# design.net
KiCad netlist of a schematic drawn in Altium Designer
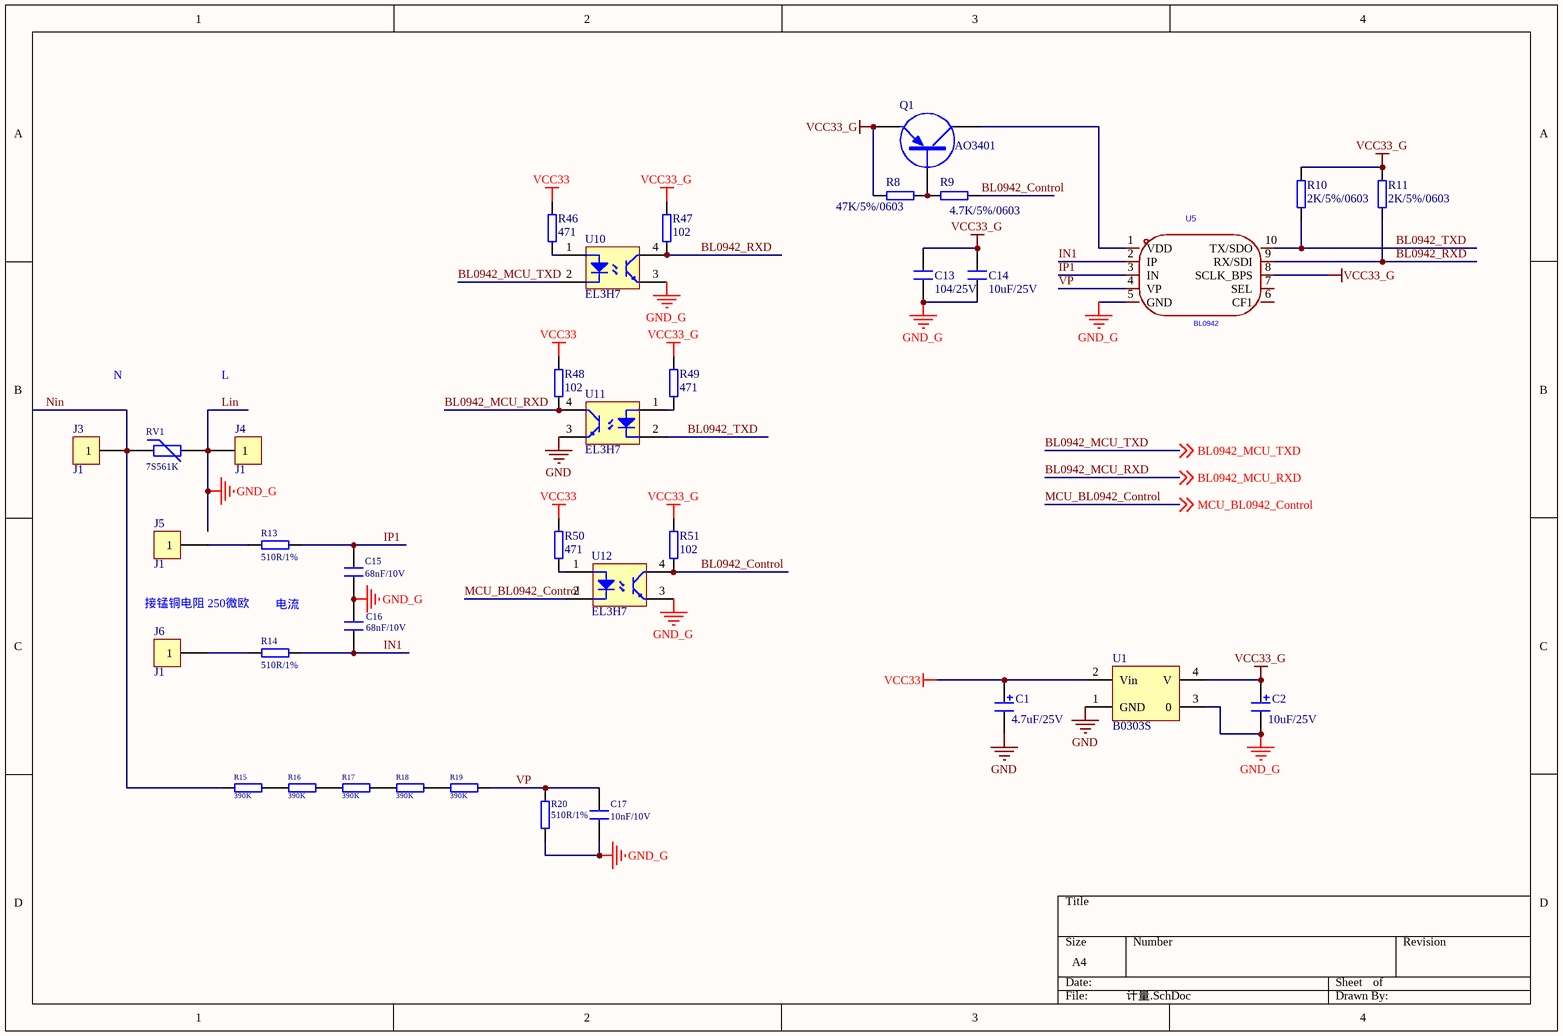
[diagram p0: 计量.SchDoc]

(export (version "E")
  (design (tool "Eeschema 10.0.6"))
  (components
    (comp (ref "C1") (value "4.7uF/25V") (footprint "0805R") (libsource (lib "ES_Schematic") (part "CAP+")))
    (comp (ref "C2") (value "10uF/25V") (footprint "0805R") (libsource (lib "ES_Schematic") (part "CAP+")))
    (comp (ref "C13") (value "104/25V") (footprint "0603R") (libsource (lib "ES_Schematic") (part "CAP_1")))
    (comp (ref "C14") (value "10uF/25V") (footprint "0603R") (libsource (lib "ES_Schematic") (part "CAP_1")))
    (comp (ref "C15") (value "68nF/10V") (footprint "0603R") (libsource (lib "ES_Schematic") (part "CAP")))
    (comp (ref "C16") (value "68nF/10V") (footprint "0603R") (libsource (lib "ES_Schematic") (part "CAP")))
    (comp (ref "C17") (value "10nF/10V") (footprint "0603R") (libsource (lib "ES_Schematic") (part "CAP")))
    (comp (ref "J3") (value "J1") (footprint "贴片焊盘V1（3*2椭圆）") (libsource (lib "") (part "J1_1")))
    (comp (ref "J4") (value "J1") (footprint "贴片焊盘V1（3*2椭圆）") (libsource (lib "ES_Schematic") (part "J1")))
    (comp (ref "J5") (value "J1") (footprint "贴片焊盘V1（3*2椭圆）") (libsource (lib "") (part "J1_1")))
    (comp (ref "J6") (value "J1") (footprint "贴片焊盘V1（3*2椭圆）") (libsource (lib "") (part "J1_1")))
    (comp (ref "Q1") (value "AO3401") (footprint "SOT-23") (libsource (lib "ES_Schematic") (part "PNP")))
    (comp (ref "R8") (value "47K/5%/0603") (footprint "0603R") (libsource (lib "ES_Schematic") (part "RES")))
    (comp (ref "R9") (value "4.7K/5%/0603") (footprint "0603R") (libsource (lib "ES_Schematic") (part "RES")))
    (comp (ref "R10") (value "2K/5%/0603") (footprint "0603R") (libsource (lib "ES_Schematic") (part "RES")))
    (comp (ref "R11") (value "2K/5%/0603") (footprint "0603R") (libsource (lib "ES_Schematic") (part "RES")))
    (comp (ref "R13") (value "510R/1%") (footprint "0603R") (libsource (lib "ES_Schematic") (part "RES")))
    (comp (ref "R14") (value "510R/1%") (footprint "0603R") (libsource (lib "ES_Schematic") (part "RES")))
    (comp (ref "R15") (value "390K") (footprint "0805R") (libsource (lib "ES_Schematic") (part "RES")))
    (comp (ref "R16") (value "390K") (footprint "0805R") (libsource (lib "ES_Schematic") (part "RES")))
    (comp (ref "R17") (value "390K") (footprint "0805R") (libsource (lib "ES_Schematic") (part "RES")))
    (comp (ref "R18") (value "390K") (footprint "0805R") (libsource (lib "ES_Schematic") (part "RES")))
    (comp (ref "R19") (value "390K") (footprint "0805R") (libsource (lib "ES_Schematic") (part "RES")))
    (comp (ref "R20") (value "510R/1%") (footprint "0603R") (libsource (lib "ES_Schematic") (part "RES")))
    (comp (ref "R46") (value "471") (footprint "0603R") (libsource (lib "ES_Schematic") (part "RES")))
    (comp (ref "R47") (value "102") (footprint "0603R") (libsource (lib "ES_Schematic") (part "RES")))
    (comp (ref "R48") (value "102") (footprint "0603R") (libsource (lib "ES_Schematic") (part "RES")))
    (comp (ref "R49") (value "471") (footprint "0603R") (libsource (lib "ES_Schematic") (part "RES")))
    (comp (ref "R50") (value "471") (footprint "0603R") (libsource (lib "ES_Schematic") (part "RES")))
    (comp (ref "R51") (value "102") (footprint "0603R") (libsource (lib "ES_Schematic") (part "RES")))
    (comp (ref "RV1")
      (value "7S561K")
      (footprint "10D821K")
      (description "Varistor (Voltage-Sensitive Resistor)")
      (fields (field (name "PUBLISHER") "Altium Limited"))
      (libsource (lib "Miscellaneous Devices") (part "Res Varistor"))
    )
    (comp (ref "U1") (value "B0303S") (footprint "B1205S-1WR3") (libsource (lib "sangjian") (part "B0505S")))
    (comp (ref "U5")
      (value "BL0942")
      (footprint "BL0942-10pin")
      (fields (field (name "MANUFACTURER") "BL(上海贝岭)"))
      (libsource (lib "altium-import") (part "root_0_BL0942_C2837510_"))
    )
    (comp (ref "U10")
      (value "EL3H7")
      (footprint "EL3H7")
      (libsource (lib "ES_Schematic") (part "Optical_Coupler_1"))
    )
    (comp (ref "U11") (value "EL3H7") (footprint "EL3H7") (libsource (lib "") (part "Optical_Coupler_1_1")))
    (comp (ref "U12")
      (value "EL3H7")
      (footprint "EL3H7")
      (libsource (lib "ES_Schematic") (part "Optical_Coupler_1"))
    )
  )
  (nets
    (net (code "1") (name "/BL0942_Control") (class "Default")
      (node (ref "R51") (pin "1") (pinfunction "1_1") (pintype "passive"))
      (node (ref "R9") (pin "2") (pinfunction "2_2") (pintype "passive"))
      (node (ref "U12") (pin "4") (pinfunction "C_4") (pintype "passive"))
    )
    (net (code "2") (name "/BL0942_RXD") (class "Default")
      (node (ref "R11") (pin "1") (pinfunction "1_1") (pintype "passive"))
      (node (ref "R47") (pin "1") (pinfunction "1_1") (pintype "passive"))
      (node (ref "U10") (pin "4") (pinfunction "C_4") (pintype "passive"))
      (node (ref "U5") (pin "9") (pinfunction "RX/SDI_9") (pintype "passive"))
    )
    (net (code "3") (name "/BL0942_TXD") (class "Default")
      (node (ref "R10") (pin "1") (pinfunction "1_1") (pintype "passive"))
      (node (ref "U11") (pin "2") (pinfunction "K_2") (pintype "passive"))
      (node (ref "U5") (pin "10") (pinfunction "TX/SDO_10") (pintype "passive"))
    )
    (net (code "4") (name "/IN1") (class "Default")
      (node (ref "C16") (pin "1") (pinfunction "1_1") (pintype "passive"))
      (node (ref "R14") (pin "2") (pinfunction "2_2") (pintype "passive"))
      (node (ref "U5") (pin "2") (pinfunction "IP_2") (pintype "passive"))
    )
    (net (code "5") (name "/IP1") (class "Default")
      (node (ref "C15") (pin "1") (pinfunction "1_1") (pintype "passive"))
      (node (ref "R13") (pin "2") (pinfunction "2_2") (pintype "passive"))
      (node (ref "U5") (pin "3") (pinfunction "IN_3") (pintype "passive"))
    )
    (net (code "6") (name "/Nin") (class "Default")
      (node (ref "J3") (pin "1") (pinfunction "1_1") (pintype "passive"))
      (node (ref "R15") (pin "2") (pinfunction "2_2") (pintype "passive"))
      (node (ref "RV1") (pin "1") (pinfunction "1_1") (pintype "passive"))
    )
    (net (code "7") (name "/VP") (class "Default")
      (node (ref "C17") (pin "1") (pinfunction "1_1") (pintype "passive"))
      (node (ref "R19") (pin "1") (pinfunction "1_1") (pintype "passive"))
      (node (ref "R20") (pin "2") (pinfunction "2_2") (pintype "passive"))
      (node (ref "U5") (pin "4") (pinfunction "VP_4") (pintype "passive"))
    )
    (net (code "8") (name "BL0942_MCU_RXD") (class "Default")
      (node (ref "R48") (pin "1") (pinfunction "1_1") (pintype "passive"))
      (node (ref "U11") (pin "4") (pinfunction "C_4") (pintype "passive"))
    )
    (net (code "9") (name "BL0942_MCU_TXD") (class "Default")
      (node (ref "U10") (pin "2") (pinfunction "K_2") (pintype "passive"))
    )
    (net (code "10") (name "GND") (class "Default")
      (node (ref "C1") (pin "2") (pinfunction "2_2") (pintype "passive"))
      (node (ref "U1") (pin "1") (pinfunction "GND_1") (pintype "passive"))
      (node (ref "U11") (pin "3") (pinfunction "E_3") (pintype "passive"))
    )
    (net (code "11") (name "GND_G") (class "Default")
      (node (ref "C13") (pin "1") (pinfunction "1_1") (pintype "passive"))
      (node (ref "C14") (pin "1") (pinfunction "1_1") (pintype "passive"))
      (node (ref "C15") (pin "2") (pinfunction "2_2") (pintype "passive"))
      (node (ref "C16") (pin "2") (pinfunction "2_2") (pintype "passive"))
      (node (ref "C17") (pin "2") (pinfunction "2_2") (pintype "passive"))
      (node (ref "C2") (pin "2") (pinfunction "2_2") (pintype "passive"))
      (node (ref "J4") (pin "1") (pinfunction "1_1") (pintype "passive"))
      (node (ref "R20") (pin "1") (pinfunction "1_1") (pintype "passive"))
      (node (ref "RV1") (pin "2") (pinfunction "2_2") (pintype "passive"))
      (node (ref "U1") (pin "3") (pinfunction "0_3") (pintype "passive"))
      (node (ref "U10") (pin "3") (pinfunction "E_3") (pintype "passive"))
      (node (ref "U12") (pin "3") (pinfunction "E_3") (pintype "passive"))
      (node (ref "U5") (pin "5") (pinfunction "GND_5") (pintype "passive"))
    )
    (net (code "12") (name "MCU_BL0942_Control") (class "Default")
      (node (ref "U12") (pin "2") (pinfunction "K_2") (pintype "passive"))
    )
    (net (code "13") (name "Net-(J5-Pad1)") (class "Default")
      (node (ref "J5") (pin "1") (pinfunction "1_1") (pintype "passive"))
      (node (ref "R13") (pin "1") (pinfunction "1_1") (pintype "passive"))
    )
    (net (code "14") (name "Net-(J6-Pad1)") (class "Default")
      (node (ref "J6") (pin "1") (pinfunction "1_1") (pintype "passive"))
      (node (ref "R14") (pin "1") (pinfunction "1_1") (pintype "passive"))
    )
    (net (code "15") (name "Net-(Q1-B)") (class "Default")
      (node (ref "Q1") (pin "1") (pinfunction "B_1") (pintype "passive"))
      (node (ref "R8") (pin "1") (pinfunction "1_1") (pintype "passive"))
      (node (ref "R9") (pin "1") (pinfunction "1_1") (pintype "passive"))
    )
    (net (code "16") (name "Net-(Q1-C)") (class "Default")
      (node (ref "Q1") (pin "3") (pinfunction "C_3") (pintype "passive"))
      (node (ref "U5") (pin "1") (pinfunction "VDD_1") (pintype "passive"))
    )
    (net (code "17") (name "Net-(R15-Pad1)") (class "Default")
      (node (ref "R15") (pin "1") (pinfunction "1_1") (pintype "passive"))
      (node (ref "R16") (pin "2") (pinfunction "2_2") (pintype "passive"))
    )
    (net (code "18") (name "Net-(R16-Pad1)") (class "Default")
      (node (ref "R16") (pin "1") (pinfunction "1_1") (pintype "passive"))
      (node (ref "R17") (pin "2") (pinfunction "2_2") (pintype "passive"))
    )
    (net (code "19") (name "Net-(R17-Pad1)") (class "Default")
      (node (ref "R17") (pin "1") (pinfunction "1_1") (pintype "passive"))
      (node (ref "R18") (pin "2") (pinfunction "2_2") (pintype "passive"))
    )
    (net (code "20") (name "Net-(R18-Pad1)") (class "Default")
      (node (ref "R18") (pin "1") (pinfunction "1_1") (pintype "passive"))
      (node (ref "R19") (pin "2") (pinfunction "2_2") (pintype "passive"))
    )
    (net (code "21") (name "Net-(U10-A)") (class "Default")
      (node (ref "R46") (pin "2") (pinfunction "2_2") (pintype "passive"))
      (node (ref "U10") (pin "1") (pinfunction "A_1") (pintype "passive"))
    )
    (net (code "22") (name "Net-(U11-A)") (class "Default")
      (node (ref "R49") (pin "2") (pinfunction "2_2") (pintype "passive"))
      (node (ref "U11") (pin "1") (pinfunction "A_1") (pintype "passive"))
    )
    (net (code "23") (name "Net-(U12-A)") (class "Default")
      (node (ref "R50") (pin "2") (pinfunction "2_2") (pintype "passive"))
      (node (ref "U12") (pin "1") (pinfunction "A_1") (pintype "passive"))
    )
    (net (code "24") (name "VCC33") (class "Default")
      (node (ref "C1") (pin "1") (pinfunction "1_1") (pintype "passive"))
      (node (ref "R46") (pin "1") (pinfunction "1_1") (pintype "passive"))
      (node (ref "R48") (pin "2") (pinfunction "2_2") (pintype "passive"))
      (node (ref "R50") (pin "1") (pinfunction "1_1") (pintype "passive"))
      (node (ref "U1") (pin "2") (pinfunction "Vin_2") (pintype "passive"))
    )
    (net (code "25") (name "VCC33_G") (class "Default")
      (node (ref "C13") (pin "2") (pinfunction "2_2") (pintype "passive"))
      (node (ref "C14") (pin "2") (pinfunction "2_2") (pintype "passive"))
      (node (ref "C2") (pin "1") (pinfunction "1_1") (pintype "passive"))
      (node (ref "Q1") (pin "2") (pinfunction "E_2") (pintype "passive"))
      (node (ref "R10") (pin "2") (pinfunction "2_2") (pintype "passive"))
      (node (ref "R11") (pin "2") (pinfunction "2_2") (pintype "passive"))
      (node (ref "R47") (pin "2") (pinfunction "2_2") (pintype "passive"))
      (node (ref "R49") (pin "1") (pinfunction "1_1") (pintype "passive"))
      (node (ref "R51") (pin "2") (pinfunction "2_2") (pintype "passive"))
      (node (ref "R8") (pin "2") (pinfunction "2_2") (pintype "passive"))
      (node (ref "U1") (pin "4") (pinfunction "V_4") (pintype "passive"))
      (node (ref "U5") (pin "8") (pinfunction "SCLK_BPS_8") (pintype "passive"))
    )
    (net (code "26") (name "unconnected-(U5-CF1-Pad6)") (class "Default")
      (node (ref "U5") (pin "6") (pinfunction "CF1_6") (pintype "passive"))
    )
    (net (code "27") (name "unconnected-(U5-SEL-Pad7)") (class "Default")
      (node (ref "U5") (pin "7") (pinfunction "SEL_7") (pintype "passive"))
    )
  )
)
